# power.net
KiCad netlist of a schematic drawn in EAGLE
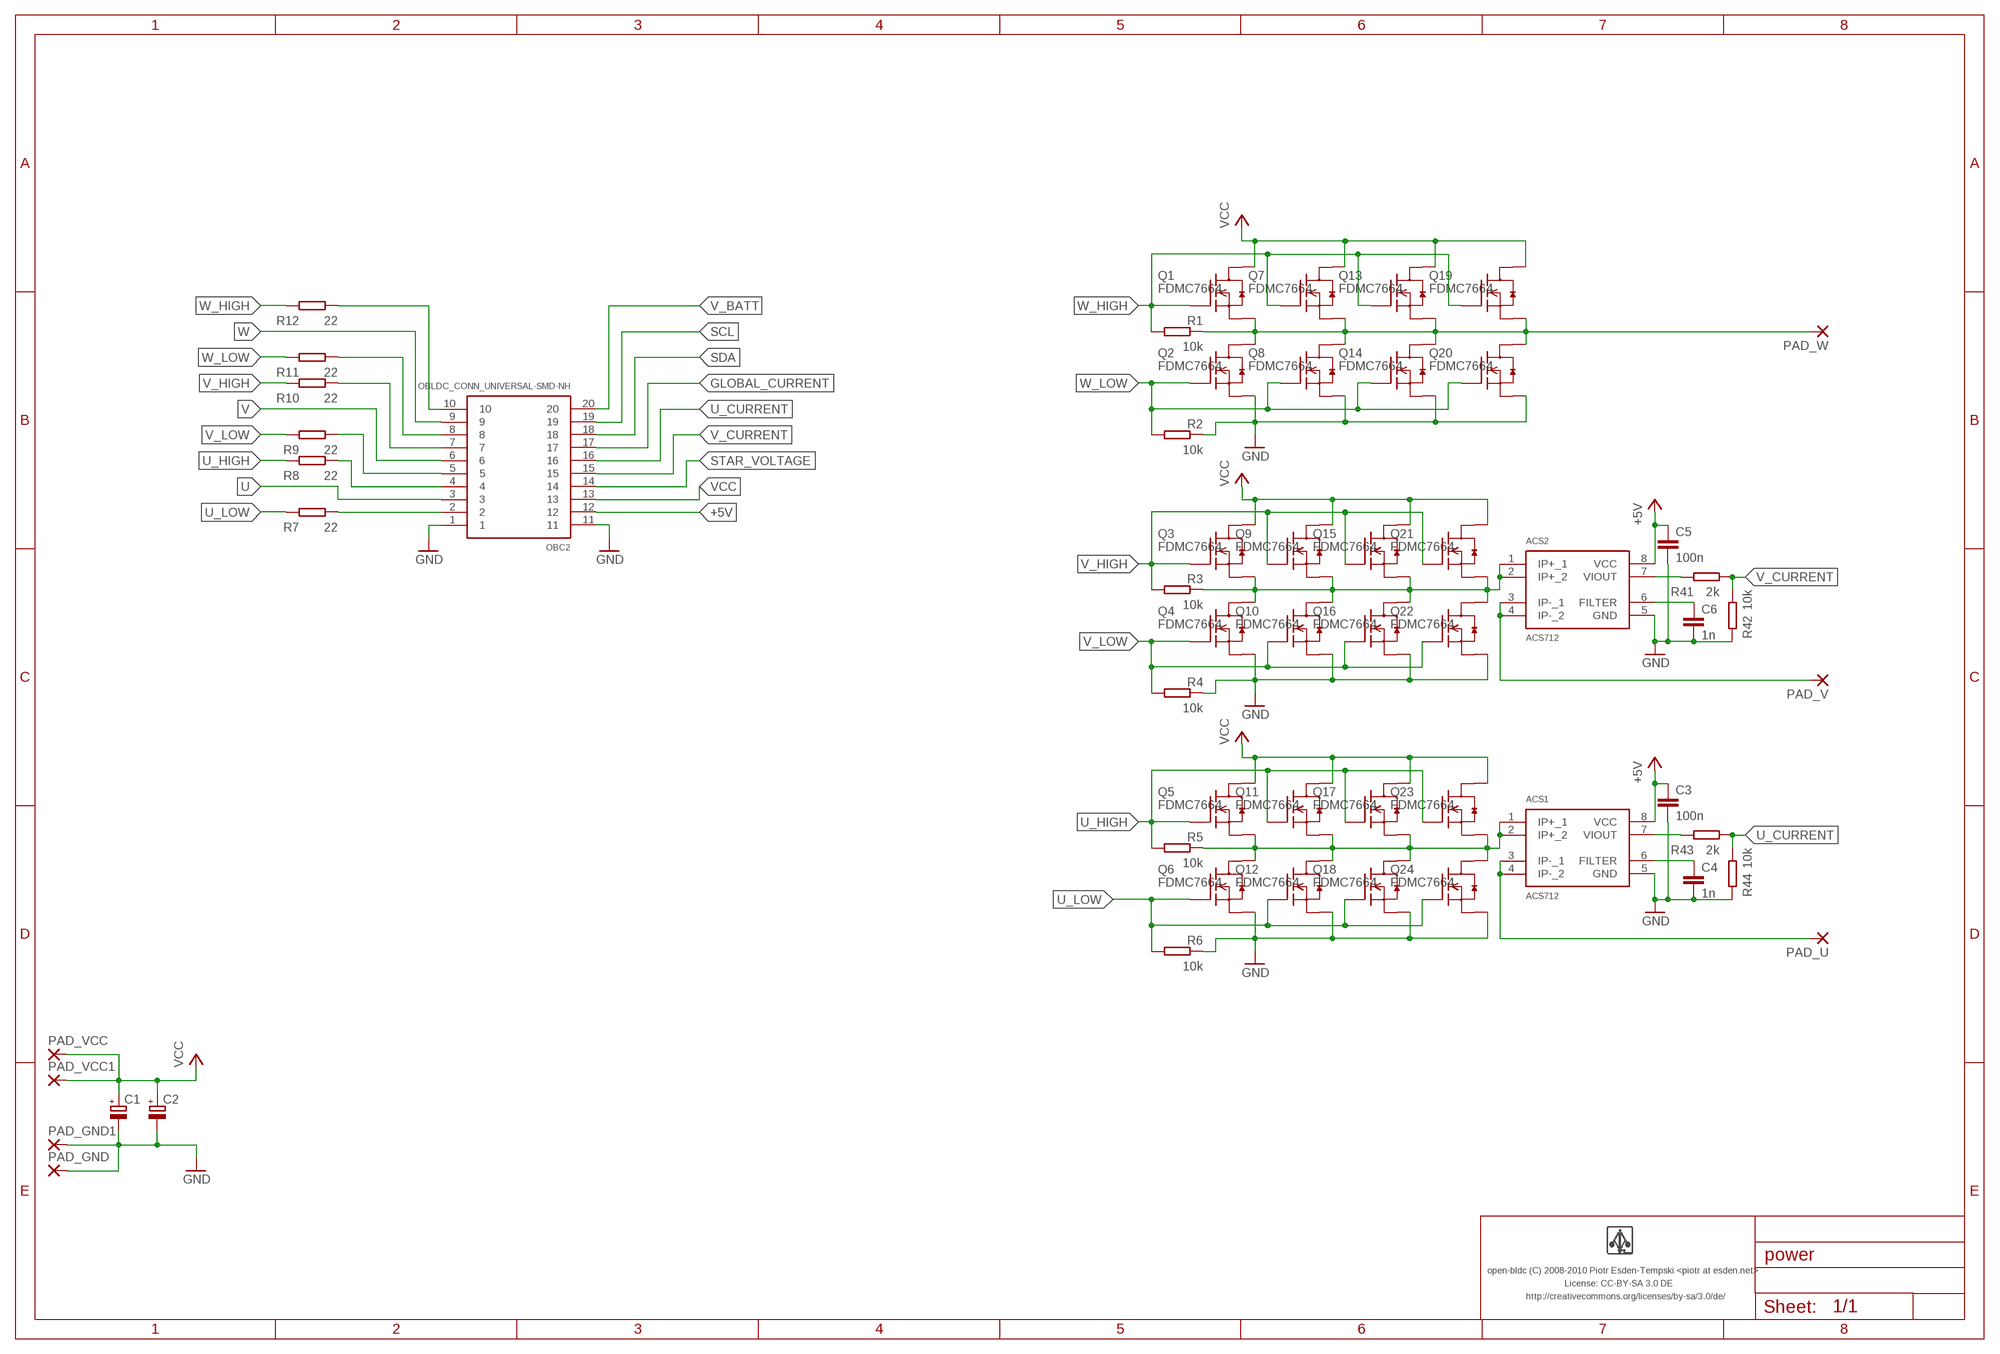
[diagram p0: schematic, sheet 1]

(export (version "E")
  (design (tool "Eeschema 10.0.6"))
  (components
    (comp (ref "ACS1")
      (value "ACS712")
      (footprint "eagle-import:SO8")
      (libsource (lib "eagle-import") (part "ACS712"))
    )
    (comp (ref "ACS2")
      (value "ACS712")
      (footprint "eagle-import:SO8")
      (libsource (lib "eagle-import") (part "ACS712"))
    )
    (comp (ref "C1")
      (value "CPOL-EUE5-10.5")
      (footprint "eagle-import:E5-10,5")
      (libsource (lib "eagle-import") (part "CPOL-EUE5-10.5"))
    )
    (comp (ref "C2")
      (value "CPOL-EUE5-10.5")
      (footprint "eagle-import:E5-10,5")
      (libsource (lib "eagle-import") (part "CPOL-EUE5-10.5"))
    )
    (comp (ref "C3")
      (value "100n")
      (footprint "eagle-import:0603-CAP")
      (libsource (lib "eagle-import") (part "CAPACITOR-0603"))
    )
    (comp (ref "C4")
      (value "1n")
      (footprint "eagle-import:0603-CAP")
      (libsource (lib "eagle-import") (part "CAPACITOR-0603"))
    )
    (comp (ref "C5")
      (value "100n")
      (footprint "eagle-import:0603-CAP")
      (libsource (lib "eagle-import") (part "CAPACITOR-0603"))
    )
    (comp (ref "C6")
      (value "1n")
      (footprint "eagle-import:0603-CAP")
      (libsource (lib "eagle-import") (part "CAPACITOR-0603"))
    )
    (comp (ref "OBC2")
      (value "OBLDC_CONN_UNIVERSAL-SMD-NH")
      (footprint "eagle-import:OBLDC_CONN_SMD_NO_HOLES")
      (libsource (lib "eagle-import") (part "OBLDC_CONN_UNIVERSAL-SMD-NH"))
    )
    (comp (ref "PAD_GND")
      (value "WIREPAD-2MM")
      (footprint "eagle-import:WIREPAD_2MM")
      (libsource (lib "eagle-import") (part "WIREPAD-2MM"))
    )
    (comp (ref "PAD_GND1")
      (value "WIREPAD-2MM")
      (footprint "eagle-import:WIREPAD_2MM")
      (libsource (lib "eagle-import") (part "WIREPAD-2MM"))
    )
    (comp (ref "PAD_U")
      (value "WIREPAD-2MM")
      (footprint "eagle-import:WIREPAD_2MM")
      (libsource (lib "eagle-import") (part "WIREPAD-2MM"))
    )
    (comp (ref "PAD_V")
      (value "WIREPAD-2MM")
      (footprint "eagle-import:WIREPAD_2MM")
      (libsource (lib "eagle-import") (part "WIREPAD-2MM"))
    )
    (comp (ref "PAD_VCC")
      (value "WIREPAD-2MM")
      (footprint "eagle-import:WIREPAD_2MM")
      (libsource (lib "eagle-import") (part "WIREPAD-2MM"))
    )
    (comp (ref "PAD_VCC1")
      (value "WIREPAD-2MM")
      (footprint "eagle-import:WIREPAD_2MM")
      (libsource (lib "eagle-import") (part "WIREPAD-2MM"))
    )
    (comp (ref "PAD_W")
      (value "WIREPAD-2MM")
      (footprint "eagle-import:WIREPAD_2MM")
      (libsource (lib "eagle-import") (part "WIREPAD-2MM"))
    )
    (comp (ref "Q1")
      (value "FDMC7664")
      (footprint "eagle-import:MLP33")
      (libsource (lib "eagle-import") (part "FDMC7664"))
    )
    (comp (ref "Q2")
      (value "FDMC7664")
      (footprint "eagle-import:MLP33")
      (libsource (lib "eagle-import") (part "FDMC7664"))
    )
    (comp (ref "Q3")
      (value "FDMC7664")
      (footprint "eagle-import:MLP33")
      (libsource (lib "eagle-import") (part "FDMC7664"))
    )
    (comp (ref "Q4")
      (value "FDMC7664")
      (footprint "eagle-import:MLP33")
      (libsource (lib "eagle-import") (part "FDMC7664"))
    )
    (comp (ref "Q5")
      (value "FDMC7664")
      (footprint "eagle-import:MLP33")
      (libsource (lib "eagle-import") (part "FDMC7664"))
    )
    (comp (ref "Q6")
      (value "FDMC7664")
      (footprint "eagle-import:MLP33")
      (libsource (lib "eagle-import") (part "FDMC7664"))
    )
    (comp (ref "Q7")
      (value "FDMC7664")
      (footprint "eagle-import:MLP33")
      (libsource (lib "eagle-import") (part "FDMC7664"))
    )
    (comp (ref "Q8")
      (value "FDMC7664")
      (footprint "eagle-import:MLP33")
      (libsource (lib "eagle-import") (part "FDMC7664"))
    )
    (comp (ref "Q9")
      (value "FDMC7664")
      (footprint "eagle-import:MLP33")
      (libsource (lib "eagle-import") (part "FDMC7664"))
    )
    (comp (ref "Q10")
      (value "FDMC7664")
      (footprint "eagle-import:MLP33")
      (libsource (lib "eagle-import") (part "FDMC7664"))
    )
    (comp (ref "Q11")
      (value "FDMC7664")
      (footprint "eagle-import:MLP33")
      (libsource (lib "eagle-import") (part "FDMC7664"))
    )
    (comp (ref "Q12")
      (value "FDMC7664")
      (footprint "eagle-import:MLP33")
      (libsource (lib "eagle-import") (part "FDMC7664"))
    )
    (comp (ref "Q13")
      (value "FDMC7664")
      (footprint "eagle-import:MLP33")
      (libsource (lib "eagle-import") (part "FDMC7664"))
    )
    (comp (ref "Q14")
      (value "FDMC7664")
      (footprint "eagle-import:MLP33")
      (libsource (lib "eagle-import") (part "FDMC7664"))
    )
    (comp (ref "Q15")
      (value "FDMC7664")
      (footprint "eagle-import:MLP33")
      (libsource (lib "eagle-import") (part "FDMC7664"))
    )
    (comp (ref "Q16")
      (value "FDMC7664")
      (footprint "eagle-import:MLP33")
      (libsource (lib "eagle-import") (part "FDMC7664"))
    )
    (comp (ref "Q17")
      (value "FDMC7664")
      (footprint "eagle-import:MLP33")
      (libsource (lib "eagle-import") (part "FDMC7664"))
    )
    (comp (ref "Q18")
      (value "FDMC7664")
      (footprint "eagle-import:MLP33")
      (libsource (lib "eagle-import") (part "FDMC7664"))
    )
    (comp (ref "Q19")
      (value "FDMC7664")
      (footprint "eagle-import:MLP33")
      (libsource (lib "eagle-import") (part "FDMC7664"))
    )
    (comp (ref "Q20")
      (value "FDMC7664")
      (footprint "eagle-import:MLP33")
      (libsource (lib "eagle-import") (part "FDMC7664"))
    )
    (comp (ref "Q21")
      (value "FDMC7664")
      (footprint "eagle-import:MLP33")
      (libsource (lib "eagle-import") (part "FDMC7664"))
    )
    (comp (ref "Q22")
      (value "FDMC7664")
      (footprint "eagle-import:MLP33")
      (libsource (lib "eagle-import") (part "FDMC7664"))
    )
    (comp (ref "Q23")
      (value "FDMC7664")
      (footprint "eagle-import:MLP33")
      (libsource (lib "eagle-import") (part "FDMC7664"))
    )
    (comp (ref "Q24")
      (value "FDMC7664")
      (footprint "eagle-import:MLP33")
      (libsource (lib "eagle-import") (part "FDMC7664"))
    )
    (comp (ref "R1")
      (value "10k")
      (footprint "eagle-import:0603-RES")
      (libsource (lib "eagle-import") (part "RESISTOR-0603"))
    )
    (comp (ref "R2")
      (value "10k")
      (footprint "eagle-import:0603-RES")
      (libsource (lib "eagle-import") (part "RESISTOR-0603"))
    )
    (comp (ref "R3")
      (value "10k")
      (footprint "eagle-import:0603-RES")
      (libsource (lib "eagle-import") (part "RESISTOR-0603"))
    )
    (comp (ref "R4")
      (value "10k")
      (footprint "eagle-import:0603-RES")
      (libsource (lib "eagle-import") (part "RESISTOR-0603"))
    )
    (comp (ref "R5")
      (value "10k")
      (footprint "eagle-import:0603-RES")
      (libsource (lib "eagle-import") (part "RESISTOR-0603"))
    )
    (comp (ref "R6")
      (value "10k")
      (footprint "eagle-import:0603-RES")
      (libsource (lib "eagle-import") (part "RESISTOR-0603"))
    )
    (comp (ref "R7")
      (value "22")
      (footprint "eagle-import:0603-RES")
      (libsource (lib "eagle-import") (part "RESISTOR-0603"))
    )
    (comp (ref "R8")
      (value "22")
      (footprint "eagle-import:0603-RES")
      (libsource (lib "eagle-import") (part "RESISTOR-0603"))
    )
    (comp (ref "R9")
      (value "22")
      (footprint "eagle-import:0603-RES")
      (libsource (lib "eagle-import") (part "RESISTOR-0603"))
    )
    (comp (ref "R10")
      (value "22")
      (footprint "eagle-import:0603-RES")
      (libsource (lib "eagle-import") (part "RESISTOR-0603"))
    )
    (comp (ref "R11")
      (value "22")
      (footprint "eagle-import:0603-RES")
      (libsource (lib "eagle-import") (part "RESISTOR-0603"))
    )
    (comp (ref "R12")
      (value "22")
      (footprint "eagle-import:0603-RES")
      (libsource (lib "eagle-import") (part "RESISTOR-0603"))
    )
    (comp (ref "R41")
      (value "2k")
      (footprint "eagle-import:0603-RES")
      (libsource (lib "eagle-import") (part "RESISTOR-0603"))
    )
    (comp (ref "R42")
      (value "10k")
      (footprint "eagle-import:0603-RES")
      (libsource (lib "eagle-import") (part "RESISTOR-0603"))
    )
    (comp (ref "R43")
      (value "2k")
      (footprint "eagle-import:0603-RES")
      (libsource (lib "eagle-import") (part "RESISTOR-0603"))
    )
    (comp (ref "R44")
      (value "10k")
      (footprint "eagle-import:0603-RES")
      (libsource (lib "eagle-import") (part "RESISTOR-0603"))
    )
    (comp (ref "U$2")
      (value "LOGO-NORM")
      (footprint "eagle-import:LOGO")
      (libsource (lib "eagle-import") (part "LOGO-NORM"))
    )
  )
  (nets
    (net (code "1") (name "+5V") (class "Default")
      (node (ref "ACS1") (pin "8") (pinfunction "VCC_8") (pintype "bidirectional"))
      (node (ref "ACS2") (pin "8") (pinfunction "VCC_8") (pintype "bidirectional"))
      (node (ref "C3") (pin "P$1") (pinfunction "1_P$1") (pintype "passive"))
      (node (ref "C5") (pin "P$1") (pinfunction "1_P$1") (pintype "passive"))
      (node (ref "OBC2") (pin "12") (pinfunction "12_12") (pintype "bidirectional"))
    )
    (net (code "2") (name "GLOBAL_CURRENT") (class "Default")
      (node (ref "OBC2") (pin "17") (pinfunction "17_17") (pintype "bidirectional"))
    )
    (net (code "3") (name "GND") (class "Default")
      (node (ref "ACS1") (pin "5") (pinfunction "GND_5") (pintype "bidirectional"))
      (node (ref "ACS2") (pin "5") (pinfunction "GND_5") (pintype "bidirectional"))
      (node (ref "C1") (pin "-") (pinfunction "-_-") (pintype "passive"))
      (node (ref "C2") (pin "-") (pinfunction "-_-") (pintype "passive"))
      (node (ref "C3") (pin "P$2") (pinfunction "2_P$2") (pintype "passive"))
      (node (ref "C4") (pin "P$2") (pinfunction "2_P$2") (pintype "passive"))
      (node (ref "C5") (pin "P$2") (pinfunction "2_P$2") (pintype "passive"))
      (node (ref "C6") (pin "P$2") (pinfunction "2_P$2") (pintype "passive"))
      (node (ref "OBC2") (pin "1") (pinfunction "1_1") (pintype "bidirectional"))
      (node (ref "OBC2") (pin "11") (pinfunction "11_11") (pintype "bidirectional"))
      (node (ref "PAD_GND") (pin "1") (pinfunction "P_1") (pintype "passive"))
      (node (ref "PAD_GND1") (pin "1") (pinfunction "P_1") (pintype "passive"))
      (node (ref "Q10") (pin "123S") (pinfunction "S_123S") (pintype "passive"))
      (node (ref "Q12") (pin "123S") (pinfunction "S_123S") (pintype "passive"))
      (node (ref "Q14") (pin "123S") (pinfunction "S_123S") (pintype "passive"))
      (node (ref "Q16") (pin "123S") (pinfunction "S_123S") (pintype "passive"))
      (node (ref "Q18") (pin "123S") (pinfunction "S_123S") (pintype "passive"))
      (node (ref "Q2") (pin "123S") (pinfunction "S_123S") (pintype "passive"))
      (node (ref "Q20") (pin "123S") (pinfunction "S_123S") (pintype "passive"))
      (node (ref "Q22") (pin "123S") (pinfunction "S_123S") (pintype "passive"))
      (node (ref "Q24") (pin "123S") (pinfunction "S_123S") (pintype "passive"))
      (node (ref "Q4") (pin "123S") (pinfunction "S_123S") (pintype "passive"))
      (node (ref "Q6") (pin "123S") (pinfunction "S_123S") (pintype "passive"))
      (node (ref "Q8") (pin "123S") (pinfunction "S_123S") (pintype "passive"))
      (node (ref "R2") (pin "P$1") (pinfunction "1_P$1") (pintype "passive"))
      (node (ref "R4") (pin "P$1") (pinfunction "1_P$1") (pintype "passive"))
      (node (ref "R42") (pin "P$2") (pinfunction "2_P$2") (pintype "passive"))
      (node (ref "R44") (pin "P$2") (pinfunction "2_P$2") (pintype "passive"))
      (node (ref "R6") (pin "P$1") (pinfunction "1_P$1") (pintype "passive"))
    )
    (net (code "4") (name "Net-(ACS1-FILTER)") (class "Default")
      (node (ref "ACS1") (pin "6") (pinfunction "FILTER_6") (pintype "bidirectional"))
      (node (ref "C4") (pin "P$1") (pinfunction "1_P$1") (pintype "passive"))
    )
    (net (code "5") (name "Net-(ACS1-IP-_1)") (class "Default")
      (node (ref "ACS1") (pin "3") (pinfunction "IP-_1_3") (pintype "bidirectional"))
      (node (ref "ACS1") (pin "4") (pinfunction "IP-_2_4") (pintype "bidirectional"))
      (node (ref "PAD_U") (pin "1") (pinfunction "P_1") (pintype "passive"))
    )
    (net (code "6") (name "Net-(ACS1-VIOUT)") (class "Default")
      (node (ref "ACS1") (pin "7") (pinfunction "VIOUT_7") (pintype "bidirectional"))
      (node (ref "R43") (pin "P$2") (pinfunction "2_P$2") (pintype "passive"))
    )
    (net (code "7") (name "Net-(ACS2-FILTER)") (class "Default")
      (node (ref "ACS2") (pin "6") (pinfunction "FILTER_6") (pintype "bidirectional"))
      (node (ref "C6") (pin "P$1") (pinfunction "1_P$1") (pintype "passive"))
    )
    (net (code "8") (name "Net-(ACS2-IP-_1)") (class "Default")
      (node (ref "ACS2") (pin "3") (pinfunction "IP-_1_3") (pintype "bidirectional"))
      (node (ref "ACS2") (pin "4") (pinfunction "IP-_2_4") (pintype "bidirectional"))
      (node (ref "PAD_V") (pin "1") (pinfunction "P_1") (pintype "passive"))
    )
    (net (code "9") (name "Net-(ACS2-VIOUT)") (class "Default")
      (node (ref "ACS2") (pin "7") (pinfunction "VIOUT_7") (pintype "bidirectional"))
      (node (ref "R41") (pin "P$2") (pinfunction "2_P$2") (pintype "passive"))
    )
    (net (code "10") (name "Net-(R7-1)") (class "Default")
      (node (ref "OBC2") (pin "2") (pinfunction "2_2") (pintype "bidirectional"))
      (node (ref "R7") (pin "P$1") (pinfunction "1_P$1") (pintype "passive"))
    )
    (net (code "11") (name "Net-(R8-1)") (class "Default")
      (node (ref "OBC2") (pin "4") (pinfunction "4_4") (pintype "bidirectional"))
      (node (ref "R8") (pin "P$1") (pinfunction "1_P$1") (pintype "passive"))
    )
    (net (code "12") (name "Net-(R9-1)") (class "Default")
      (node (ref "OBC2") (pin "5") (pinfunction "5_5") (pintype "bidirectional"))
      (node (ref "R9") (pin "P$1") (pinfunction "1_P$1") (pintype "passive"))
    )
    (net (code "13") (name "Net-(R10-1)") (class "Default")
      (node (ref "OBC2") (pin "7") (pinfunction "7_7") (pintype "bidirectional"))
      (node (ref "R10") (pin "P$1") (pinfunction "1_P$1") (pintype "passive"))
    )
    (net (code "14") (name "Net-(R11-1)") (class "Default")
      (node (ref "OBC2") (pin "8") (pinfunction "8_8") (pintype "bidirectional"))
      (node (ref "R11") (pin "P$1") (pinfunction "1_P$1") (pintype "passive"))
    )
    (net (code "15") (name "Net-(R12-1)") (class "Default")
      (node (ref "OBC2") (pin "10") (pinfunction "10_10") (pintype "bidirectional"))
      (node (ref "R12") (pin "P$1") (pinfunction "1_P$1") (pintype "passive"))
    )
    (net (code "16") (name "SCL") (class "Default")
      (node (ref "OBC2") (pin "19") (pinfunction "19_19") (pintype "bidirectional"))
    )
    (net (code "17") (name "SDA") (class "Default")
      (node (ref "OBC2") (pin "18") (pinfunction "18_18") (pintype "bidirectional"))
    )
    (net (code "18") (name "STAR_VOLTAGE") (class "Default")
      (node (ref "OBC2") (pin "14") (pinfunction "14_14") (pintype "bidirectional"))
    )
    (net (code "19") (name "U") (class "Default")
      (node (ref "ACS1") (pin "1") (pinfunction "IP+_1_1") (pintype "bidirectional"))
      (node (ref "ACS1") (pin "2") (pinfunction "IP+_2_2") (pintype "bidirectional"))
      (node (ref "OBC2") (pin "3") (pinfunction "3_3") (pintype "bidirectional"))
      (node (ref "Q11") (pin "123S") (pinfunction "S_123S") (pintype "passive"))
      (node (ref "Q12") (pin "5678D") (pinfunction "D_5678D") (pintype "passive"))
      (node (ref "Q17") (pin "123S") (pinfunction "S_123S") (pintype "passive"))
      (node (ref "Q18") (pin "5678D") (pinfunction "D_5678D") (pintype "passive"))
      (node (ref "Q23") (pin "123S") (pinfunction "S_123S") (pintype "passive"))
      (node (ref "Q24") (pin "5678D") (pinfunction "D_5678D") (pintype "passive"))
      (node (ref "Q5") (pin "123S") (pinfunction "S_123S") (pintype "passive"))
      (node (ref "Q6") (pin "5678D") (pinfunction "D_5678D") (pintype "passive"))
      (node (ref "R5") (pin "P$1") (pinfunction "1_P$1") (pintype "passive"))
    )
    (net (code "20") (name "U_CURRENT") (class "Default")
      (node (ref "OBC2") (pin "16") (pinfunction "16_16") (pintype "bidirectional"))
      (node (ref "R43") (pin "P$1") (pinfunction "1_P$1") (pintype "passive"))
      (node (ref "R44") (pin "P$1") (pinfunction "1_P$1") (pintype "passive"))
    )
    (net (code "21") (name "U_HIGH") (class "Default")
      (node (ref "Q11") (pin "4G") (pinfunction "G_4G") (pintype "passive"))
      (node (ref "Q17") (pin "4G") (pinfunction "G_4G") (pintype "passive"))
      (node (ref "Q23") (pin "4G") (pinfunction "G_4G") (pintype "passive"))
      (node (ref "Q5") (pin "4G") (pinfunction "G_4G") (pintype "passive"))
      (node (ref "R5") (pin "P$2") (pinfunction "2_P$2") (pintype "passive"))
      (node (ref "R8") (pin "P$2") (pinfunction "2_P$2") (pintype "passive"))
    )
    (net (code "22") (name "U_LOW") (class "Default")
      (node (ref "Q12") (pin "4G") (pinfunction "G_4G") (pintype "passive"))
      (node (ref "Q18") (pin "4G") (pinfunction "G_4G") (pintype "passive"))
      (node (ref "Q24") (pin "4G") (pinfunction "G_4G") (pintype "passive"))
      (node (ref "Q6") (pin "4G") (pinfunction "G_4G") (pintype "passive"))
      (node (ref "R6") (pin "P$2") (pinfunction "2_P$2") (pintype "passive"))
      (node (ref "R7") (pin "P$2") (pinfunction "2_P$2") (pintype "passive"))
    )
    (net (code "23") (name "V") (class "Default")
      (node (ref "ACS2") (pin "1") (pinfunction "IP+_1_1") (pintype "bidirectional"))
      (node (ref "ACS2") (pin "2") (pinfunction "IP+_2_2") (pintype "bidirectional"))
      (node (ref "OBC2") (pin "6") (pinfunction "6_6") (pintype "bidirectional"))
      (node (ref "Q10") (pin "5678D") (pinfunction "D_5678D") (pintype "passive"))
      (node (ref "Q15") (pin "123S") (pinfunction "S_123S") (pintype "passive"))
      (node (ref "Q16") (pin "5678D") (pinfunction "D_5678D") (pintype "passive"))
      (node (ref "Q21") (pin "123S") (pinfunction "S_123S") (pintype "passive"))
      (node (ref "Q22") (pin "5678D") (pinfunction "D_5678D") (pintype "passive"))
      (node (ref "Q3") (pin "123S") (pinfunction "S_123S") (pintype "passive"))
      (node (ref "Q4") (pin "5678D") (pinfunction "D_5678D") (pintype "passive"))
      (node (ref "Q9") (pin "123S") (pinfunction "S_123S") (pintype "passive"))
      (node (ref "R3") (pin "P$1") (pinfunction "1_P$1") (pintype "passive"))
    )
    (net (code "24") (name "VCC") (class "Default")
      (node (ref "C1") (pin "+") (pinfunction "+_+") (pintype "passive"))
      (node (ref "C2") (pin "+") (pinfunction "+_+") (pintype "passive"))
      (node (ref "OBC2") (pin "13") (pinfunction "13_13") (pintype "bidirectional"))
      (node (ref "PAD_VCC") (pin "1") (pinfunction "P_1") (pintype "passive"))
      (node (ref "PAD_VCC1") (pin "1") (pinfunction "P_1") (pintype "passive"))
      (node (ref "Q1") (pin "5678D") (pinfunction "D_5678D") (pintype "passive"))
      (node (ref "Q11") (pin "5678D") (pinfunction "D_5678D") (pintype "passive"))
      (node (ref "Q13") (pin "5678D") (pinfunction "D_5678D") (pintype "passive"))
      (node (ref "Q15") (pin "5678D") (pinfunction "D_5678D") (pintype "passive"))
      (node (ref "Q17") (pin "5678D") (pinfunction "D_5678D") (pintype "passive"))
      (node (ref "Q19") (pin "5678D") (pinfunction "D_5678D") (pintype "passive"))
      (node (ref "Q21") (pin "5678D") (pinfunction "D_5678D") (pintype "passive"))
      (node (ref "Q23") (pin "5678D") (pinfunction "D_5678D") (pintype "passive"))
      (node (ref "Q3") (pin "5678D") (pinfunction "D_5678D") (pintype "passive"))
      (node (ref "Q5") (pin "5678D") (pinfunction "D_5678D") (pintype "passive"))
      (node (ref "Q7") (pin "5678D") (pinfunction "D_5678D") (pintype "passive"))
      (node (ref "Q9") (pin "5678D") (pinfunction "D_5678D") (pintype "passive"))
    )
    (net (code "25") (name "V_BATT") (class "Default")
      (node (ref "OBC2") (pin "20") (pinfunction "20_20") (pintype "bidirectional"))
    )
    (net (code "26") (name "V_CURRENT") (class "Default")
      (node (ref "OBC2") (pin "15") (pinfunction "15_15") (pintype "bidirectional"))
      (node (ref "R41") (pin "P$1") (pinfunction "1_P$1") (pintype "passive"))
      (node (ref "R42") (pin "P$1") (pinfunction "1_P$1") (pintype "passive"))
    )
    (net (code "27") (name "V_HIGH") (class "Default")
      (node (ref "Q15") (pin "4G") (pinfunction "G_4G") (pintype "passive"))
      (node (ref "Q21") (pin "4G") (pinfunction "G_4G") (pintype "passive"))
      (node (ref "Q3") (pin "4G") (pinfunction "G_4G") (pintype "passive"))
      (node (ref "Q9") (pin "4G") (pinfunction "G_4G") (pintype "passive"))
      (node (ref "R10") (pin "P$2") (pinfunction "2_P$2") (pintype "passive"))
      (node (ref "R3") (pin "P$2") (pinfunction "2_P$2") (pintype "passive"))
    )
    (net (code "28") (name "V_LOW") (class "Default")
      (node (ref "Q10") (pin "4G") (pinfunction "G_4G") (pintype "passive"))
      (node (ref "Q16") (pin "4G") (pinfunction "G_4G") (pintype "passive"))
      (node (ref "Q22") (pin "4G") (pinfunction "G_4G") (pintype "passive"))
      (node (ref "Q4") (pin "4G") (pinfunction "G_4G") (pintype "passive"))
      (node (ref "R4") (pin "P$2") (pinfunction "2_P$2") (pintype "passive"))
      (node (ref "R9") (pin "P$2") (pinfunction "2_P$2") (pintype "passive"))
    )
    (net (code "29") (name "W") (class "Default")
      (node (ref "OBC2") (pin "9") (pinfunction "9_9") (pintype "bidirectional"))
      (node (ref "PAD_W") (pin "1") (pinfunction "P_1") (pintype "passive"))
      (node (ref "Q1") (pin "123S") (pinfunction "S_123S") (pintype "passive"))
      (node (ref "Q13") (pin "123S") (pinfunction "S_123S") (pintype "passive"))
      (node (ref "Q14") (pin "5678D") (pinfunction "D_5678D") (pintype "passive"))
      (node (ref "Q19") (pin "123S") (pinfunction "S_123S") (pintype "passive"))
      (node (ref "Q2") (pin "5678D") (pinfunction "D_5678D") (pintype "passive"))
      (node (ref "Q20") (pin "5678D") (pinfunction "D_5678D") (pintype "passive"))
      (node (ref "Q7") (pin "123S") (pinfunction "S_123S") (pintype "passive"))
      (node (ref "Q8") (pin "5678D") (pinfunction "D_5678D") (pintype "passive"))
      (node (ref "R1") (pin "P$1") (pinfunction "1_P$1") (pintype "passive"))
    )
    (net (code "30") (name "W_HIGH") (class "Default")
      (node (ref "Q1") (pin "4G") (pinfunction "G_4G") (pintype "passive"))
      (node (ref "Q13") (pin "4G") (pinfunction "G_4G") (pintype "passive"))
      (node (ref "Q19") (pin "4G") (pinfunction "G_4G") (pintype "passive"))
      (node (ref "Q7") (pin "4G") (pinfunction "G_4G") (pintype "passive"))
      (node (ref "R1") (pin "P$2") (pinfunction "2_P$2") (pintype "passive"))
      (node (ref "R12") (pin "P$2") (pinfunction "2_P$2") (pintype "passive"))
    )
    (net (code "31") (name "W_LOW") (class "Default")
      (node (ref "Q14") (pin "4G") (pinfunction "G_4G") (pintype "passive"))
      (node (ref "Q2") (pin "4G") (pinfunction "G_4G") (pintype "passive"))
      (node (ref "Q20") (pin "4G") (pinfunction "G_4G") (pintype "passive"))
      (node (ref "Q8") (pin "4G") (pinfunction "G_4G") (pintype "passive"))
      (node (ref "R11") (pin "P$2") (pinfunction "2_P$2") (pintype "passive"))
      (node (ref "R2") (pin "P$2") (pinfunction "2_P$2") (pintype "passive"))
    )
  )
)
